# yard-ice-fpga.net
KiCad netlist of a schematic drawn in Altium Designer
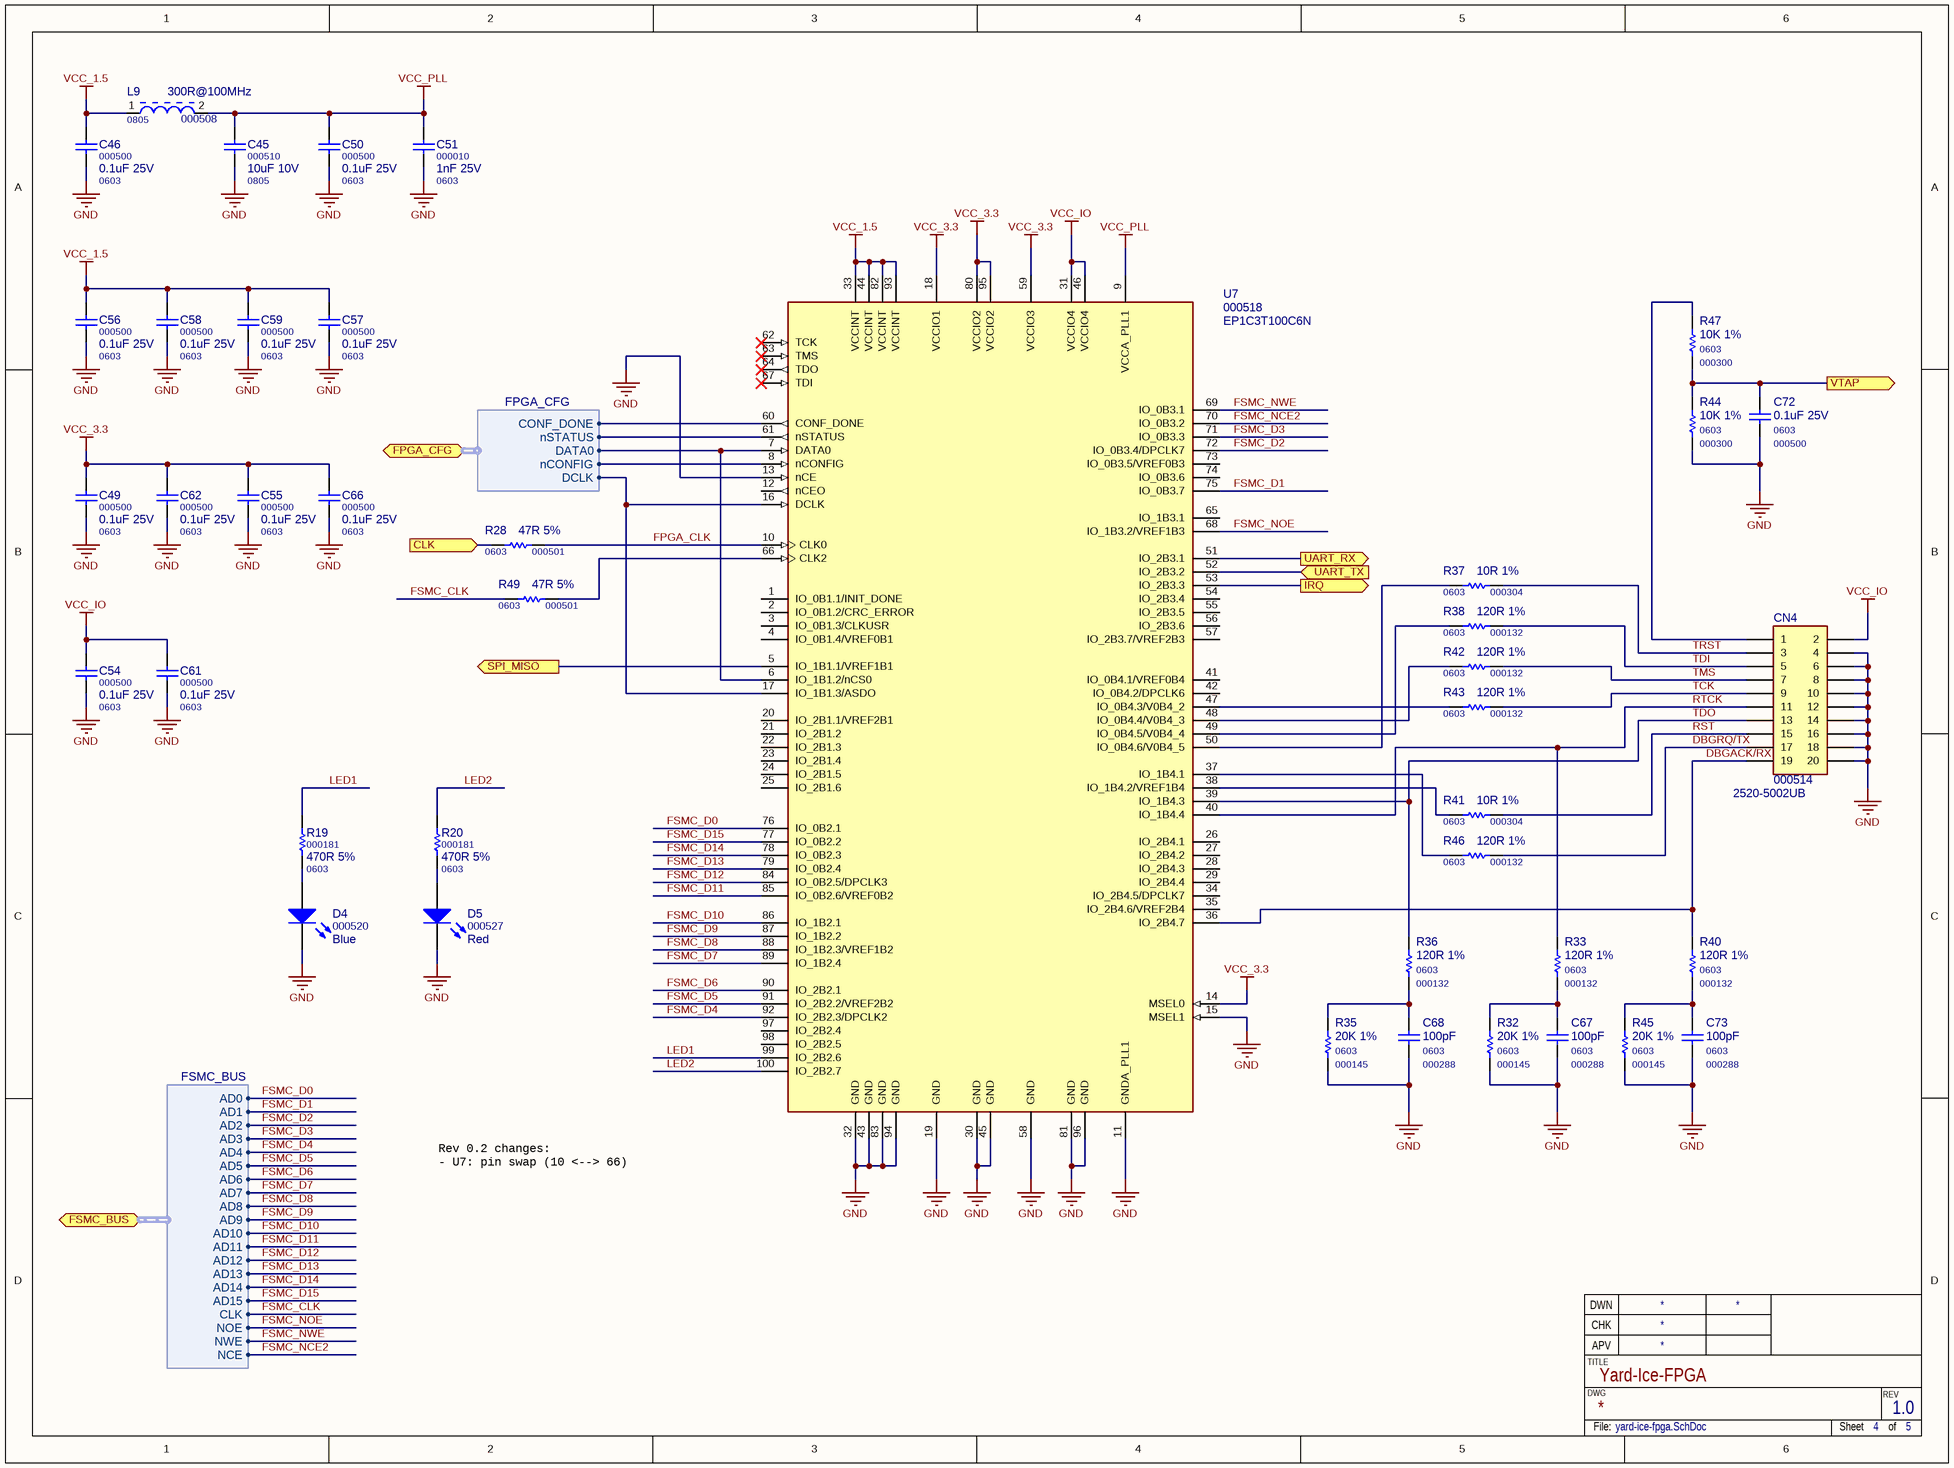
[diagram p0: yard-ice-fpga.SchDoc]

(export (version "E")
  (design (tool "Eeschema 10.0.6"))
  (components
    (comp (ref "C45")
      (value "000510")
      (footprint "C0805M")
      (description "SMD Ceramic Chip Capacitor - 0805 - X7R")
      (fields
        (field (name "ALTIUM_VALUE") "10uF 10V")
        (field (name "PACKAGE") "0805")
        (field (name "MF") "TDK")
      )
      (libsource (lib "discrete-sm") (part "C0805"))
    )
    (comp (ref "C46")
      (value "000500")
      (footprint "C0603M")
      (description "SMD Ceramic Chip Capacitor - 0603 - X7R")
      (fields
        (field (name "ALTIUM_VALUE") "0.1uF 25V")
        (field (name "PACKAGE") "0603")
        (field (name "MF") "TDK")
      )
      (libsource (lib "discrete-sm") (part "C0603"))
    )
    (comp (ref "C49")
      (value "000500")
      (footprint "C0603M")
      (description "SMD Ceramic Chip Capacitor - 0603 - X7R")
      (fields
        (field (name "ALTIUM_VALUE") "0.1uF 25V")
        (field (name "PACKAGE") "0603")
        (field (name "MF") "TDK")
      )
      (libsource (lib "discrete-sm") (part "C0603"))
    )
    (comp (ref "C50")
      (value "000500")
      (footprint "C0603M")
      (description "SMD Ceramic Chip Capacitor - 0603 - X7R")
      (fields
        (field (name "ALTIUM_VALUE") "0.1uF 25V")
        (field (name "PACKAGE") "0603")
        (field (name "MF") "TDK")
      )
      (libsource (lib "discrete-sm") (part "C0603"))
    )
    (comp (ref "C51")
      (value "000010")
      (footprint "C0603M")
      (description "SMD Ceramic Chip Capacitor - 0603 - X7R")
      (fields (field (name "ALTIUM_VALUE") "1nF 25V") (field (name "PACKAGE") "0603"))
      (libsource (lib "discrete-sm") (part "C0603"))
    )
    (comp (ref "C54")
      (value "000500")
      (footprint "C0603M")
      (description "SMD Ceramic Chip Capacitor - 0603 - X7R")
      (fields
        (field (name "ALTIUM_VALUE") "0.1uF 25V")
        (field (name "PACKAGE") "0603")
        (field (name "MF") "TDK")
      )
      (libsource (lib "discrete-sm") (part "C0603"))
    )
    (comp (ref "C55")
      (value "000500")
      (footprint "C0603M")
      (description "SMD Ceramic Chip Capacitor - 0603 - X7R")
      (fields
        (field (name "ALTIUM_VALUE") "0.1uF 25V")
        (field (name "PACKAGE") "0603")
        (field (name "MF") "TDK")
      )
      (libsource (lib "discrete-sm") (part "C0603"))
    )
    (comp (ref "C56")
      (value "000500")
      (footprint "C0603M")
      (description "SMD Ceramic Chip Capacitor - 0603 - X7R")
      (fields
        (field (name "ALTIUM_VALUE") "0.1uF 25V")
        (field (name "PACKAGE") "0603")
        (field (name "MF") "TDK")
      )
      (libsource (lib "discrete-sm") (part "C0603"))
    )
    (comp (ref "C57")
      (value "000500")
      (footprint "C0603M")
      (description "SMD Ceramic Chip Capacitor - 0603 - X7R")
      (fields
        (field (name "ALTIUM_VALUE") "0.1uF 25V")
        (field (name "PACKAGE") "0603")
        (field (name "MF") "TDK")
      )
      (libsource (lib "discrete-sm") (part "C0603"))
    )
    (comp (ref "C58")
      (value "000500")
      (footprint "C0603M")
      (description "SMD Ceramic Chip Capacitor - 0603 - X7R")
      (fields
        (field (name "ALTIUM_VALUE") "0.1uF 25V")
        (field (name "PACKAGE") "0603")
        (field (name "MF") "TDK")
      )
      (libsource (lib "discrete-sm") (part "C0603"))
    )
    (comp (ref "C59")
      (value "000500")
      (footprint "C0603M")
      (description "SMD Ceramic Chip Capacitor - 0603 - X7R")
      (fields
        (field (name "ALTIUM_VALUE") "0.1uF 25V")
        (field (name "PACKAGE") "0603")
        (field (name "MF") "TDK")
      )
      (libsource (lib "discrete-sm") (part "C0603"))
    )
    (comp (ref "C61")
      (value "000500")
      (footprint "C0603M")
      (description "SMD Ceramic Chip Capacitor - 0603 - X7R")
      (fields
        (field (name "ALTIUM_VALUE") "0.1uF 25V")
        (field (name "PACKAGE") "0603")
        (field (name "MF") "TDK")
      )
      (libsource (lib "discrete-sm") (part "C0603"))
    )
    (comp (ref "C62")
      (value "000500")
      (footprint "C0603M")
      (description "SMD Ceramic Chip Capacitor - 0603 - X7R")
      (fields
        (field (name "ALTIUM_VALUE") "0.1uF 25V")
        (field (name "PACKAGE") "0603")
        (field (name "MF") "TDK")
      )
      (libsource (lib "discrete-sm") (part "C0603"))
    )
    (comp (ref "C66")
      (value "000500")
      (footprint "C0603M")
      (description "SMD Ceramic Chip Capacitor - 0603 - X7R")
      (fields
        (field (name "ALTIUM_VALUE") "0.1uF 25V")
        (field (name "PACKAGE") "0603")
        (field (name "MF") "TDK")
      )
      (libsource (lib "discrete-sm") (part "C0603"))
    )
    (comp (ref "C67")
      (value "000288")
      (footprint "C0603M")
      (description "SMD Ceramic Chip Capacitor - 0603")
      (fields (field (name "ALTIUM_VALUE") "100pF") (field (name "PACKAGE") "0603"))
      (libsource (lib "discrete-sm") (part "C0603"))
    )
    (comp (ref "C68")
      (value "000288")
      (footprint "C0603M")
      (description "SMD Ceramic Chip Capacitor - 0603")
      (fields (field (name "ALTIUM_VALUE") "100pF") (field (name "PACKAGE") "0603"))
      (libsource (lib "discrete-sm") (part "C0603"))
    )
    (comp (ref "C72")
      (value "000500")
      (footprint "C0603M")
      (description "SMD Ceramic Chip Capacitor - 0603 - X7R")
      (fields
        (field (name "ALTIUM_VALUE") "0.1uF 25V")
        (field (name "PACKAGE") "0603")
        (field (name "MF") "TDK")
      )
      (libsource (lib "discrete-sm") (part "C0603"))
    )
    (comp (ref "C73")
      (value "000288")
      (footprint "C0603M")
      (description "SMD Ceramic Chip Capacitor - 0603")
      (fields (field (name "ALTIUM_VALUE") "100pF") (field (name "PACKAGE") "0603"))
      (libsource (lib "discrete-sm") (part "C0603"))
    )
    (comp (ref "CN4")
      (value "000514")
      (footprint "TST-110-04-G-D-RA")
      (description "Shrouded Header, 20 Pos, Right Angle")
      (fields (field (name "ALTIUM_VALUE") "2520-5002UB") (field (name "MF") "3M"))
      (libsource (lib "samtec-board-to-board") (part "Header 10X2"))
    )
    (comp (ref "D4")
      (value "000520")
      (footprint "LED0805L LP")
      (description "LED SMD 0805")
      (fields (field (name "ALTIUM_VALUE") "Blue"))
      (libsource (lib "discrete-sm") (part "LED0805LP"))
    )
    (comp (ref "D5")
      (value "000527")
      (footprint "LED0805L LP")
      (description "LED SMD 0805")
      (fields (field (name "ALTIUM_VALUE") "Red"))
      (libsource (lib "discrete-sm") (part "LED0805LP"))
    )
    (comp (ref "L9")
      (value "000508")
      (footprint "L0805M")
      (description "SMD Ferrite Bead 0805")
      (fields
        (field (name "ALTIUM_VALUE") "300R@100MHz")
        (field (name "PACKAGE") "0805")
        (field (name "MF") "TDK")
      )
      (libsource (lib "discrete-sm") (part "L0805"))
    )
    (comp (ref "R19")
      (value "000181")
      (footprint "R0603M")
      (description "SMD Chip Resistor - 0603")
      (fields (field (name "ALTIUM_VALUE") "470R 5%") (field (name "PACKAGE") "0603"))
      (libsource (lib "discrete-sm") (part "R0603"))
    )
    (comp (ref "R20")
      (value "000181")
      (footprint "R0603M")
      (description "SMD Chip Resistor - 0603")
      (fields (field (name "ALTIUM_VALUE") "470R 5%") (field (name "PACKAGE") "0603"))
      (libsource (lib "discrete-sm") (part "R0603"))
    )
    (comp (ref "R28")
      (value "000501")
      (footprint "R0603M")
      (description "SMD Chip Resistor - 0603")
      (fields (field (name "ALTIUM_VALUE") "47R 5%") (field (name "PACKAGE") "0603"))
      (libsource (lib "discrete-sm") (part "R0603"))
    )
    (comp (ref "R32")
      (value "000145")
      (footprint "R0603M")
      (description "SMD Chip Resistor - 0603")
      (fields (field (name "ALTIUM_VALUE") "20K 1%") (field (name "PACKAGE") "0603"))
      (libsource (lib "discrete-sm") (part "R0603"))
    )
    (comp (ref "R33")
      (value "000132")
      (footprint "R0603M")
      (description "SMD Chip Resistor - 0603")
      (fields (field (name "ALTIUM_VALUE") "120R 1%") (field (name "PACKAGE") "0603"))
      (libsource (lib "discrete-sm") (part "R0603"))
    )
    (comp (ref "R35")
      (value "000145")
      (footprint "R0603M")
      (description "SMD Chip Resistor - 0603")
      (fields (field (name "ALTIUM_VALUE") "20K 1%") (field (name "PACKAGE") "0603"))
      (libsource (lib "discrete-sm") (part "R0603"))
    )
    (comp (ref "R36")
      (value "000132")
      (footprint "R0603M")
      (description "SMD Chip Resistor - 0603")
      (fields (field (name "ALTIUM_VALUE") "120R 1%") (field (name "PACKAGE") "0603"))
      (libsource (lib "discrete-sm") (part "R0603"))
    )
    (comp (ref "R37")
      (value "000304")
      (footprint "R0603M")
      (description "SMD Chip Resistor - 0603")
      (fields (field (name "ALTIUM_VALUE") "10R 1%") (field (name "PACKAGE") "0603"))
      (libsource (lib "discrete-sm") (part "R0603"))
    )
    (comp (ref "R38")
      (value "000132")
      (footprint "R0603M")
      (description "SMD Chip Resistor - 0603")
      (fields (field (name "ALTIUM_VALUE") "120R 1%") (field (name "PACKAGE") "0603"))
      (libsource (lib "discrete-sm") (part "R0603"))
    )
    (comp (ref "R40")
      (value "000132")
      (footprint "R0603M")
      (description "SMD Chip Resistor - 0603")
      (fields (field (name "ALTIUM_VALUE") "120R 1%") (field (name "PACKAGE") "0603"))
      (libsource (lib "discrete-sm") (part "R0603"))
    )
    (comp (ref "R41")
      (value "000304")
      (footprint "R0603M")
      (description "SMD Chip Resistor - 0603")
      (fields (field (name "ALTIUM_VALUE") "10R 1%") (field (name "PACKAGE") "0603"))
      (libsource (lib "discrete-sm") (part "R0603"))
    )
    (comp (ref "R42")
      (value "000132")
      (footprint "R0603M")
      (description "SMD Chip Resistor - 0603")
      (fields (field (name "ALTIUM_VALUE") "120R 1%") (field (name "PACKAGE") "0603"))
      (libsource (lib "discrete-sm") (part "R0603"))
    )
    (comp (ref "R43")
      (value "000132")
      (footprint "R0603M")
      (description "SMD Chip Resistor - 0603")
      (fields (field (name "ALTIUM_VALUE") "120R 1%") (field (name "PACKAGE") "0603"))
      (libsource (lib "discrete-sm") (part "R0603"))
    )
    (comp (ref "R44")
      (value "000300")
      (footprint "R0603M")
      (description "SMD Chip Resistor - 0603")
      (fields (field (name "ALTIUM_VALUE") "10K 1%") (field (name "PACKAGE") "0603"))
      (libsource (lib "discrete-sm") (part "R0603"))
    )
    (comp (ref "R45")
      (value "000145")
      (footprint "R0603M")
      (description "SMD Chip Resistor - 0603")
      (fields (field (name "ALTIUM_VALUE") "20K 1%") (field (name "PACKAGE") "0603"))
      (libsource (lib "discrete-sm") (part "R0603"))
    )
    (comp (ref "R46")
      (value "000132")
      (footprint "R0603M")
      (description "SMD Chip Resistor - 0603")
      (fields (field (name "ALTIUM_VALUE") "120R 1%") (field (name "PACKAGE") "0603"))
      (libsource (lib "discrete-sm") (part "R0603"))
    )
    (comp (ref "R47")
      (value "000300")
      (footprint "R0603M")
      (description "SMD Chip Resistor - 0603")
      (fields (field (name "ALTIUM_VALUE") "10K 1%") (field (name "PACKAGE") "0603"))
      (libsource (lib "discrete-sm") (part "R0603"))
    )
    (comp (ref "R49")
      (value "000501")
      (footprint "R0603M")
      (description "SMD Chip Resistor - 0603")
      (fields (field (name "ALTIUM_VALUE") "47R 5%") (field (name "PACKAGE") "0603"))
      (libsource (lib "discrete-sm") (part "R0603"))
    )
    (comp (ref "U7")
      (value "000518")
      (footprint "TQFP-100")
      (description "Cyclone FPGA")
      (fields (field (name "ALTIUM_VALUE") "EP1C3T100C6N") (field (name "MF") "Altera"))
      (libsource (lib "altera-cyclone") (part "EP1C3T100C8N"))
    )
  )
  (nets
    (net (code "3") (name "/CLK") (class "Default")
      (node (ref "R28") (pin "2") (pinfunction "2_2") (pintype "passive"))
    )
    (net (code "4") (name "/CONF_DONE") (class "Default")
      (node (ref "U7") (pin "60") (pinfunction "CONF_DONE_60") (pintype "output"))
    )
    (net (code "5") (name "/DATA0") (class "Default")
      (node (ref "U7") (pin "6") (pinfunction "IO_1B1.2/nCS0_6") (pintype "tri_state"))
      (node (ref "U7") (pin "7") (pinfunction "DATA0_7") (pintype "input"))
    )
    (net (code "6") (name "/DBGACK{slash}RX") (class "Default")
      (node (ref "CN4") (pin "19") (pinfunction "19_19") (pintype "passive"))
      (node (ref "R40") (pin "1") (pinfunction "1_1") (pintype "passive"))
      (node (ref "U7") (pin "36") (pinfunction "IO_2B4.7_36") (pintype "tri_state"))
    )
    (net (code "7") (name "/DBGRQ{slash}TX") (class "Default")
      (node (ref "CN4") (pin "17") (pinfunction "17_17") (pintype "passive"))
      (node (ref "R46") (pin "1") (pinfunction "1_1") (pintype "passive"))
    )
    (net (code "8") (name "/DCLK") (class "Default")
      (node (ref "U7") (pin "16") (pinfunction "DCLK_16") (pintype "input"))
      (node (ref "U7") (pin "17") (pinfunction "IO_1B1.3/ASDO_17") (pintype "tri_state"))
    )
    (net (code "9") (name "/FPGA_CLK") (class "Default")
      (node (ref "R28") (pin "1") (pinfunction "1_1") (pintype "passive"))
      (node (ref "U7") (pin "10") (pinfunction "CLK0_10") (pintype "input"))
    )
    (net (code "10") (name "/FSMC_CLK") (class "Default")
      (node (ref "R49") (pin "2") (pinfunction "2_2") (pintype "passive"))
    )
    (net (code "11") (name "/FSMC_D0") (class "Default")
      (node (ref "U7") (pin "76") (pinfunction "IO_0B2.1_76") (pintype "tri_state"))
    )
    (net (code "12") (name "/FSMC_D1") (class "Default")
      (node (ref "U7") (pin "75") (pinfunction "IO_0B3.7_75") (pintype "tri_state"))
    )
    (net (code "13") (name "/FSMC_D2") (class "Default")
      (node (ref "U7") (pin "72") (pinfunction "IO_0B3.4/DPCLK7_72") (pintype "tri_state"))
    )
    (net (code "14") (name "/FSMC_D3") (class "Default")
      (node (ref "U7") (pin "71") (pinfunction "IO_0B3.3_71") (pintype "tri_state"))
    )
    (net (code "15") (name "/FSMC_D4") (class "Default")
      (node (ref "U7") (pin "92") (pinfunction "IO_2B2.3/DPCLK2_92") (pintype "tri_state"))
    )
    (net (code "16") (name "/FSMC_D5") (class "Default")
      (node (ref "U7") (pin "91") (pinfunction "IO_2B2.2/VREF2B2_91") (pintype "tri_state"))
    )
    (net (code "17") (name "/FSMC_D6") (class "Default")
      (node (ref "U7") (pin "90") (pinfunction "IO_2B2.1_90") (pintype "tri_state"))
    )
    (net (code "18") (name "/FSMC_D7") (class "Default")
      (node (ref "U7") (pin "89") (pinfunction "IO_1B2.4_89") (pintype "tri_state"))
    )
    (net (code "19") (name "/FSMC_D8") (class "Default")
      (node (ref "U7") (pin "88") (pinfunction "IO_1B2.3/VREF1B2_88") (pintype "tri_state"))
    )
    (net (code "20") (name "/FSMC_D9") (class "Default")
      (node (ref "U7") (pin "87") (pinfunction "IO_1B2.2_87") (pintype "tri_state"))
    )
    (net (code "21") (name "/FSMC_D10") (class "Default")
      (node (ref "U7") (pin "86") (pinfunction "IO_1B2.1_86") (pintype "tri_state"))
    )
    (net (code "22") (name "/FSMC_D11") (class "Default")
      (node (ref "U7") (pin "85") (pinfunction "IO_0B2.6/VREF0B2_85") (pintype "tri_state"))
    )
    (net (code "23") (name "/FSMC_D12") (class "Default")
      (node (ref "U7") (pin "84") (pinfunction "IO_0B2.5/DPCLK3_84") (pintype "tri_state"))
    )
    (net (code "24") (name "/FSMC_D13") (class "Default")
      (node (ref "U7") (pin "79") (pinfunction "IO_0B2.4_79") (pintype "tri_state"))
    )
    (net (code "25") (name "/FSMC_D14") (class "Default")
      (node (ref "U7") (pin "78") (pinfunction "IO_0B2.3_78") (pintype "tri_state"))
    )
    (net (code "26") (name "/FSMC_D15") (class "Default")
      (node (ref "U7") (pin "77") (pinfunction "IO_0B2.2_77") (pintype "tri_state"))
    )
    (net (code "27") (name "/FSMC_NCE2") (class "Default")
      (node (ref "U7") (pin "70") (pinfunction "IO_0B3.2_70") (pintype "tri_state"))
    )
    (net (code "28") (name "/FSMC_NOE") (class "Default")
      (node (ref "U7") (pin "68") (pinfunction "IO_1B3.2/VREF1B3_68") (pintype "tri_state"))
    )
    (net (code "29") (name "/FSMC_NWE") (class "Default")
      (node (ref "U7") (pin "69") (pinfunction "IO_0B3.1_69") (pintype "tri_state"))
    )
    (net (code "30") (name "/IRQ") (class "Default")
      (node (ref "U7") (pin "53") (pinfunction "IO_2B3.3_53") (pintype "tri_state"))
    )
    (net (code "31") (name "/LED1") (class "Default")
      (node (ref "R19") (pin "1") (pinfunction "1_1") (pintype "passive"))
      (node (ref "U7") (pin "99") (pinfunction "IO_2B2.6_99") (pintype "tri_state"))
    )
    (net (code "32") (name "/LED2") (class "Default")
      (node (ref "R20") (pin "1") (pinfunction "1_1") (pintype "passive"))
      (node (ref "U7") (pin "100") (pinfunction "IO_2B2.7_100") (pintype "tri_state"))
    )
    (net (code "33") (name "/RST") (class "Default")
      (node (ref "CN4") (pin "15") (pinfunction "15_15") (pintype "passive"))
      (node (ref "R41") (pin "1") (pinfunction "1_1") (pintype "passive"))
    )
    (net (code "34") (name "/RTCK") (class "Default")
      (node (ref "CN4") (pin "11") (pinfunction "11_11") (pintype "passive"))
      (node (ref "R33") (pin "1") (pinfunction "1_1") (pintype "passive"))
      (node (ref "U7") (pin "40") (pinfunction "IO_1B4.4_40") (pintype "tri_state"))
    )
    (net (code "35") (name "/SPI_MISO") (class "Default")
      (node (ref "U7") (pin "5") (pinfunction "IO_1B1.1/VREF1B1_5") (pintype "tri_state"))
    )
    (net (code "36") (name "/TCK") (class "Default")
      (node (ref "CN4") (pin "9") (pinfunction "9_9") (pintype "passive"))
      (node (ref "R43") (pin "1") (pinfunction "1_1") (pintype "passive"))
    )
    (net (code "37") (name "/TDI") (class "Default")
      (node (ref "CN4") (pin "5") (pinfunction "5_5") (pintype "passive"))
      (node (ref "R38") (pin "1") (pinfunction "1_1") (pintype "passive"))
    )
    (net (code "38") (name "/TDO") (class "Default")
      (node (ref "CN4") (pin "13") (pinfunction "13_13") (pintype "passive"))
      (node (ref "R36") (pin "1") (pinfunction "1_1") (pintype "passive"))
      (node (ref "U7") (pin "39") (pinfunction "IO_1B4.3_39") (pintype "tri_state"))
    )
    (net (code "39") (name "/TMS") (class "Default")
      (node (ref "CN4") (pin "7") (pinfunction "7_7") (pintype "passive"))
      (node (ref "R42") (pin "1") (pinfunction "1_1") (pintype "passive"))
    )
    (net (code "40") (name "/TRST") (class "Default")
      (node (ref "CN4") (pin "3") (pinfunction "3_3") (pintype "passive"))
      (node (ref "R37") (pin "1") (pinfunction "1_1") (pintype "passive"))
    )
    (net (code "41") (name "/UART_RX") (class "Default")
      (node (ref "U7") (pin "51") (pinfunction "IO_2B3.1_51") (pintype "tri_state"))
    )
    (net (code "42") (name "/UART_TX") (class "Default")
      (node (ref "U7") (pin "52") (pinfunction "IO_2B3.2_52") (pintype "tri_state"))
    )
    (net (code "43") (name "/VTAP") (class "Default")
      (node (ref "C72") (pin "1") (pinfunction "1_1") (pintype "passive"))
      (node (ref "R44") (pin "1") (pinfunction "1_1") (pintype "passive"))
      (node (ref "R47") (pin "2") (pinfunction "2_2") (pintype "passive"))
    )
    (net (code "44") (name "/nCONFIG") (class "Default")
      (node (ref "U7") (pin "8") (pinfunction "nCONFIG_8") (pintype "input"))
    )
    (net (code "45") (name "/nSTATUS") (class "Default")
      (node (ref "U7") (pin "61") (pinfunction "nSTATUS_61") (pintype "output"))
    )
    (net (code "48") (name "GND") (class "Default")
      (node (ref "C45") (pin "2") (pinfunction "2_2") (pintype "passive"))
      (node (ref "C46") (pin "2") (pinfunction "2_2") (pintype "passive"))
      (node (ref "C49") (pin "2") (pinfunction "2_2") (pintype "passive"))
      (node (ref "C50") (pin "2") (pinfunction "2_2") (pintype "passive"))
      (node (ref "C51") (pin "2") (pinfunction "2_2") (pintype "passive"))
      (node (ref "C54") (pin "2") (pinfunction "2_2") (pintype "passive"))
      (node (ref "C55") (pin "2") (pinfunction "2_2") (pintype "passive"))
      (node (ref "C56") (pin "2") (pinfunction "2_2") (pintype "passive"))
      (node (ref "C57") (pin "2") (pinfunction "2_2") (pintype "passive"))
      (node (ref "C58") (pin "2") (pinfunction "2_2") (pintype "passive"))
      (node (ref "C59") (pin "2") (pinfunction "2_2") (pintype "passive"))
      (node (ref "C61") (pin "2") (pinfunction "2_2") (pintype "passive"))
      (node (ref "C62") (pin "2") (pinfunction "2_2") (pintype "passive"))
      (node (ref "C66") (pin "2") (pinfunction "2_2") (pintype "passive"))
      (node (ref "C67") (pin "2") (pinfunction "2_2") (pintype "passive"))
      (node (ref "C68") (pin "2") (pinfunction "2_2") (pintype "passive"))
      (node (ref "C72") (pin "2") (pinfunction "2_2") (pintype "passive"))
      (node (ref "C73") (pin "2") (pinfunction "2_2") (pintype "passive"))
      (node (ref "CN4") (pin "10") (pinfunction "10_10") (pintype "passive"))
      (node (ref "CN4") (pin "12") (pinfunction "12_12") (pintype "passive"))
      (node (ref "CN4") (pin "14") (pinfunction "14_14") (pintype "passive"))
      (node (ref "CN4") (pin "16") (pinfunction "16_16") (pintype "passive"))
      (node (ref "CN4") (pin "18") (pinfunction "18_18") (pintype "passive"))
      (node (ref "CN4") (pin "20") (pinfunction "20_20") (pintype "passive"))
      (node (ref "CN4") (pin "4") (pinfunction "4_4") (pintype "passive"))
      (node (ref "CN4") (pin "6") (pinfunction "6_6") (pintype "passive"))
      (node (ref "CN4") (pin "8") (pinfunction "8_8") (pintype "passive"))
      (node (ref "D4") (pin "2") (pinfunction "K_2") (pintype "passive"))
      (node (ref "D5") (pin "2") (pinfunction "K_2") (pintype "passive"))
      (node (ref "R32") (pin "2") (pinfunction "2_2") (pintype "passive"))
      (node (ref "R35") (pin "2") (pinfunction "2_2") (pintype "passive"))
      (node (ref "R44") (pin "2") (pinfunction "2_2") (pintype "passive"))
      (node (ref "R45") (pin "2") (pinfunction "2_2") (pintype "passive"))
      (node (ref "U7") (pin "11") (pinfunction "GNDA_PLL1_11") (pintype "power_in"))
      (node (ref "U7") (pin "13") (pinfunction "nCE_13") (pintype "input"))
      (node (ref "U7") (pin "15") (pinfunction "MSEL1_15") (pintype "input"))
      (node (ref "U7") (pin "19") (pinfunction "GND_19") (pintype "power_in"))
      (node (ref "U7") (pin "30") (pinfunction "GND_30") (pintype "power_in"))
      (node (ref "U7") (pin "32") (pinfunction "GND_32") (pintype "power_in"))
      (node (ref "U7") (pin "43") (pinfunction "GND_43") (pintype "power_in"))
      (node (ref "U7") (pin "45") (pinfunction "GND_45") (pintype "power_in"))
      (node (ref "U7") (pin "58") (pinfunction "GND_58") (pintype "power_in"))
      (node (ref "U7") (pin "81") (pinfunction "GND_81") (pintype "power_in"))
      (node (ref "U7") (pin "83") (pinfunction "GND_83") (pintype "power_in"))
      (node (ref "U7") (pin "94") (pinfunction "GND_94") (pintype "power_in"))
      (node (ref "U7") (pin "96") (pinfunction "GND_96") (pintype "power_in"))
    )
    (net (code "49") (name "Net-(C67-Pad1)") (class "Default")
      (node (ref "C67") (pin "1") (pinfunction "1_1") (pintype "passive"))
      (node (ref "R32") (pin "1") (pinfunction "1_1") (pintype "passive"))
      (node (ref "R33") (pin "2") (pinfunction "2_2") (pintype "passive"))
    )
    (net (code "50") (name "Net-(C68-Pad1)") (class "Default")
      (node (ref "C68") (pin "1") (pinfunction "1_1") (pintype "passive"))
      (node (ref "R35") (pin "1") (pinfunction "1_1") (pintype "passive"))
      (node (ref "R36") (pin "2") (pinfunction "2_2") (pintype "passive"))
    )
    (net (code "51") (name "Net-(C73-Pad1)") (class "Default")
      (node (ref "C73") (pin "1") (pinfunction "1_1") (pintype "passive"))
      (node (ref "R40") (pin "2") (pinfunction "2_2") (pintype "passive"))
      (node (ref "R45") (pin "1") (pinfunction "1_1") (pintype "passive"))
    )
    (net (code "52") (name "Net-(CN4-Pad1)") (class "Default")
      (node (ref "CN4") (pin "1") (pinfunction "1_1") (pintype "passive"))
      (node (ref "R47") (pin "1") (pinfunction "1_1") (pintype "passive"))
    )
    (net (code "53") (name "Net-(D4-A)") (class "Default")
      (node (ref "D4") (pin "1") (pinfunction "A_1") (pintype "passive"))
      (node (ref "R19") (pin "2") (pinfunction "2_2") (pintype "passive"))
    )
    (net (code "54") (name "Net-(D5-A)") (class "Default")
      (node (ref "D5") (pin "1") (pinfunction "A_1") (pintype "passive"))
      (node (ref "R20") (pin "2") (pinfunction "2_2") (pintype "passive"))
    )
    (net (code "55") (name "Net-(U7-CLK2)") (class "Default")
      (node (ref "R49") (pin "1") (pinfunction "1_1") (pintype "passive"))
      (node (ref "U7") (pin "66") (pinfunction "CLK2_66") (pintype "input"))
    )
    (net (code "56") (name "Net-(U7-IO_0B4.3{slash}V0B4_2)") (class "Default")
      (node (ref "R43") (pin "2") (pinfunction "2_2") (pintype "passive"))
      (node (ref "U7") (pin "47") (pinfunction "IO_0B4.3/V0B4_2_47") (pintype "tri_state"))
    )
    (net (code "57") (name "Net-(U7-IO_0B4.4{slash}V0B4_3)") (class "Default")
      (node (ref "R42") (pin "2") (pinfunction "2_2") (pintype "passive"))
      (node (ref "U7") (pin "48") (pinfunction "IO_0B4.4/V0B4_3_48") (pintype "tri_state"))
    )
    (net (code "58") (name "Net-(U7-IO_0B4.5{slash}V0B4_4)") (class "Default")
      (node (ref "R38") (pin "2") (pinfunction "2_2") (pintype "passive"))
      (node (ref "U7") (pin "49") (pinfunction "IO_0B4.5/V0B4_4_49") (pintype "tri_state"))
    )
    (net (code "59") (name "Net-(U7-IO_0B4.6{slash}V0B4_5)") (class "Default")
      (node (ref "R37") (pin "2") (pinfunction "2_2") (pintype "passive"))
      (node (ref "U7") (pin "50") (pinfunction "IO_0B4.6/V0B4_5_50") (pintype "tri_state"))
    )
    (net (code "60") (name "Net-(U7-IO_1B4.1)") (class "Default")
      (node (ref "R46") (pin "2") (pinfunction "2_2") (pintype "passive"))
      (node (ref "U7") (pin "37") (pinfunction "IO_1B4.1_37") (pintype "tri_state"))
    )
    (net (code "61") (name "Net-(U7-IO_1B4.2{slash}VREF1B4)") (class "Default")
      (node (ref "R41") (pin "2") (pinfunction "2_2") (pintype "passive"))
      (node (ref "U7") (pin "38") (pinfunction "IO_1B4.2/VREF1B4_38") (pintype "tri_state"))
    )
    (net (code "62") (name "VCC_1.5") (class "Default")
      (node (ref "C46") (pin "1") (pinfunction "1_1") (pintype "passive"))
      (node (ref "C56") (pin "1") (pinfunction "1_1") (pintype "passive"))
      (node (ref "C57") (pin "1") (pinfunction "1_1") (pintype "passive"))
      (node (ref "C58") (pin "1") (pinfunction "1_1") (pintype "passive"))
      (node (ref "C59") (pin "1") (pinfunction "1_1") (pintype "passive"))
      (node (ref "L9") (pin "1") (pinfunction "1_1") (pintype "passive"))
      (node (ref "U7") (pin "33") (pinfunction "VCCINT_33") (pintype "power_in"))
      (node (ref "U7") (pin "44") (pinfunction "VCCINT_44") (pintype "power_in"))
      (node (ref "U7") (pin "82") (pinfunction "VCCINT_82") (pintype "power_in"))
      (node (ref "U7") (pin "93") (pinfunction "VCCINT_93") (pintype "power_in"))
    )
    (net (code "63") (name "VCC_3.3") (class "Default")
      (node (ref "C49") (pin "1") (pinfunction "1_1") (pintype "passive"))
      (node (ref "C55") (pin "1") (pinfunction "1_1") (pintype "passive"))
      (node (ref "C62") (pin "1") (pinfunction "1_1") (pintype "passive"))
      (node (ref "C66") (pin "1") (pinfunction "1_1") (pintype "passive"))
      (node (ref "U7") (pin "14") (pinfunction "MSEL0_14") (pintype "input"))
      (node (ref "U7") (pin "18") (pinfunction "VCCIO1_18") (pintype "power_in"))
      (node (ref "U7") (pin "59") (pinfunction "VCCIO3_59") (pintype "power_in"))
      (node (ref "U7") (pin "80") (pinfunction "VCCIO2_80") (pintype "power_in"))
      (node (ref "U7") (pin "95") (pinfunction "VCCIO2_95") (pintype "power_in"))
    )
    (net (code "64") (name "VCC_IO") (class "Default")
      (node (ref "C54") (pin "1") (pinfunction "1_1") (pintype "passive"))
      (node (ref "C61") (pin "1") (pinfunction "1_1") (pintype "passive"))
      (node (ref "CN4") (pin "2") (pinfunction "2_2") (pintype "passive"))
      (node (ref "U7") (pin "31") (pinfunction "VCCIO4_31") (pintype "power_in"))
      (node (ref "U7") (pin "46") (pinfunction "VCCIO4_46") (pintype "power_in"))
    )
    (net (code "65") (name "VCC_PLL") (class "Default")
      (node (ref "C45") (pin "1") (pinfunction "1_1") (pintype "passive"))
      (node (ref "C50") (pin "1") (pinfunction "1_1") (pintype "passive"))
      (node (ref "C51") (pin "1") (pinfunction "1_1") (pintype "passive"))
      (node (ref "L9") (pin "2") (pinfunction "2_2") (pintype "passive"))
      (node (ref "U7") (pin "9") (pinfunction "VCCA_PLL1_9") (pintype "power_in"))
    )
    (net (code "66") (name "unconnected-(U7-IO_0B1.1{slash}INIT_DONE-Pad1)") (class "Default")
      (node (ref "U7") (pin "1") (pinfunction "IO_0B1.1/INIT_DONE_1") (pintype "tri_state"))
    )
    (net (code "67") (name "unconnected-(U7-IO_0B1.2{slash}CRC_ERROR-Pad2)") (class "Default")
      (node (ref "U7") (pin "2") (pinfunction "IO_0B1.2/CRC_ERROR_2") (pintype "tri_state"))
    )
    (net (code "68") (name "unconnected-(U7-IO_0B1.3{slash}CLKUSR-Pad3)") (class "Default")
      (node (ref "U7") (pin "3") (pinfunction "IO_0B1.3/CLKUSR_3") (pintype "tri_state"))
    )
    (net (code "69") (name "unconnected-(U7-IO_0B1.4{slash}VREF0B1-Pad4)") (class "Default")
      (node (ref "U7") (pin "4") (pinfunction "IO_0B1.4/VREF0B1_4") (pintype "tri_state"))
    )
    (net (code "70") (name "unconnected-(U7-IO_0B3.5{slash}VREF0B3-Pad73)") (class "Default")
      (node (ref "U7") (pin "73") (pinfunction "IO_0B3.5/VREF0B3_73") (pintype "tri_state"))
    )
    (net (code "71") (name "unconnected-(U7-IO_0B3.6-Pad74)") (class "Default")
      (node (ref "U7") (pin "74") (pinfunction "IO_0B3.6_74") (pintype "tri_state"))
    )
    (net (code "72") (name "unconnected-(U7-IO_0B4.1{slash}VREF0B4-Pad41)") (class "Default")
      (node (ref "U7") (pin "41") (pinfunction "IO_0B4.1/VREF0B4_41") (pintype "tri_state"))
    )
    (net (code "73") (name "unconnected-(U7-IO_0B4.2{slash}DPCLK6-Pad42)") (class "Default")
      (node (ref "U7") (pin "42") (pinfunction "IO_0B4.2/DPCLK6_42") (pintype "tri_state"))
    )
    (net (code "74") (name "unconnected-(U7-IO_1B3.1-Pad65)") (class "Default")
      (node (ref "U7") (pin "65") (pinfunction "IO_1B3.1_65") (pintype "tri_state"))
    )
    (net (code "75") (name "unconnected-(U7-IO_2B1.1{slash}VREF2B1-Pad20)") (class "Default")
      (node (ref "U7") (pin "20") (pinfunction "IO_2B1.1/VREF2B1_20") (pintype "tri_state"))
    )
    (net (code "76") (name "unconnected-(U7-IO_2B1.2-Pad21)") (class "Default")
      (node (ref "U7") (pin "21") (pinfunction "IO_2B1.2_21") (pintype "tri_state"))
    )
    (net (code "77") (name "unconnected-(U7-IO_2B1.3-Pad22)") (class "Default")
      (node (ref "U7") (pin "22") (pinfunction "IO_2B1.3_22") (pintype "tri_state"))
    )
    (net (code "78") (name "unconnected-(U7-IO_2B1.4-Pad23)") (class "Default")
      (node (ref "U7") (pin "23") (pinfunction "IO_2B1.4_23") (pintype "tri_state"))
    )
    (net (code "79") (name "unconnected-(U7-IO_2B1.5-Pad24)") (class "Default")
      (node (ref "U7") (pin "24") (pinfunction "IO_2B1.5_24") (pintype "tri_state"))
    )
    (net (code "80") (name "unconnected-(U7-IO_2B1.6-Pad25)") (class "Default")
      (node (ref "U7") (pin "25") (pinfunction "IO_2B1.6_25") (pintype "tri_state"))
    )
    (net (code "81") (name "unconnected-(U7-IO_2B2.4-Pad97)") (class "Default")
      (node (ref "U7") (pin "97") (pinfunction "IO_2B2.4_97") (pintype "tri_state"))
    )
    (net (code "82") (name "unconnected-(U7-IO_2B2.5-Pad98)") (class "Default")
      (node (ref "U7") (pin "98") (pinfunction "IO_2B2.5_98") (pintype "tri_state"))
    )
    (net (code "83") (name "unconnected-(U7-IO_2B3.4-Pad54)") (class "Default")
      (node (ref "U7") (pin "54") (pinfunction "IO_2B3.4_54") (pintype "tri_state"))
    )
    (net (code "84") (name "unconnected-(U7-IO_2B3.5-Pad55)") (class "Default")
      (node (ref "U7") (pin "55") (pinfunction "IO_2B3.5_55") (pintype "tri_state"))
    )
    (net (code "85") (name "unconnected-(U7-IO_2B3.6-Pad56)") (class "Default")
      (node (ref "U7") (pin "56") (pinfunction "IO_2B3.6_56") (pintype "tri_state"))
    )
    (net (code "86") (name "unconnected-(U7-IO_2B3.7{slash}VREF2B3-Pad57)") (class "Default")
      (node (ref "U7") (pin "57") (pinfunction "IO_2B3.7/VREF2B3_57") (pintype "tri_state"))
    )
    (net (code "87") (name "unconnected-(U7-IO_2B4.1-Pad26)") (class "Default")
      (node (ref "U7") (pin "26") (pinfunction "IO_2B4.1_26") (pintype "tri_state"))
    )
    (net (code "88") (name "unconnected-(U7-IO_2B4.2-Pad27)") (class "Default")
      (node (ref "U7") (pin "27") (pinfunction "IO_2B4.2_27") (pintype "tri_state"))
    )
    (net (code "89") (name "unconnected-(U7-IO_2B4.3-Pad28)") (class "Default")
      (node (ref "U7") (pin "28") (pinfunction "IO_2B4.3_28") (pintype "tri_state"))
    )
    (net (code "90") (name "unconnected-(U7-IO_2B4.4-Pad29)") (class "Default")
      (node (ref "U7") (pin "29") (pinfunction "IO_2B4.4_29") (pintype "tri_state"))
    )
    (net (code "91") (name "unconnected-(U7-IO_2B4.5{slash}DPCLK7-Pad34)") (class "Default")
      (node (ref "U7") (pin "34") (pinfunction "IO_2B4.5/DPCLK7_34") (pintype "tri_state"))
    )
    (net (code "92") (name "unconnected-(U7-IO_2B4.6{slash}VREF2B4-Pad35)") (class "Default")
      (node (ref "U7") (pin "35") (pinfunction "IO_2B4.6/VREF2B4_35") (pintype "tri_state"))
    )
    (net (code "93") (name "unconnected-(U7-TCK-Pad62)") (class "Default")
      (node (ref "U7") (pin "62") (pinfunction "TCK_62") (pintype "input+no_connect"))
    )
    (net (code "94") (name "unconnected-(U7-TDI-Pad67)") (class "Default")
      (node (ref "U7") (pin "67") (pinfunction "TDI_67") (pintype "input+no_connect"))
    )
    (net (code "95") (name "unconnected-(U7-TDO-Pad64)") (class "Default")
      (node (ref "U7") (pin "64") (pinfunction "TDO_64") (pintype "output+no_connect"))
    )
    (net (code "96") (name "unconnected-(U7-TMS-Pad63)") (class "Default")
      (node (ref "U7") (pin "63") (pinfunction "TMS_63") (pintype "input+no_connect"))
    )
    (net (code "97") (name "unconnected-(U7-nCEO-Pad12)") (class "Default")
      (node (ref "U7") (pin "12") (pinfunction "nCEO_12") (pintype "output"))
    )
  )
)
